# adapter.net
KiCad netlist of a schematic drawn in EAGLE
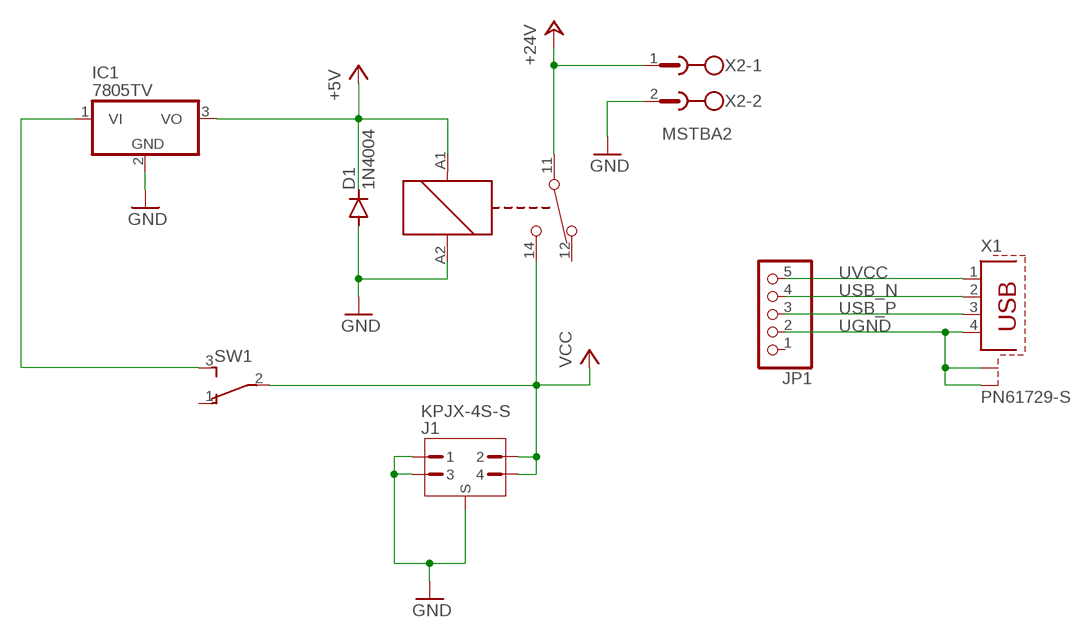
[diagram p0: schematic, sheet 1]

(export (version "E")
  (design (tool "Eeschema 10.0.6"))
  (components
    (comp (ref "D1")
      (value "1N4004")
      (footprint "eagle-import:DO41-10")
      (libsource (lib "eagle-import") (part "1N4004"))
    )
    (comp (ref "IC1")
      (value "7805TV")
      (footprint "eagle-import:TO220V")
      (libsource (lib "eagle-import") (part "78TV05"))
    )
    (comp (ref "J1")
      (value "KPJX-4S-S")
      (footprint "eagle-import:KPJX-4S-S")
      (libsource (lib "eagle-import") (part "KPJX-4S-S"))
    )
    (comp (ref "JP1")
      (value "PINHD-1X5/90")
      (footprint "eagle-import:1X05_90")
      (libsource (lib "eagle-import") (part "PINHD-1X5/90"))
    )
    (comp (ref "K1")
      (value "36.11.9.005.4011")
      (footprint "eagle-import:36.11-4011")
      (libsource (lib "eagle-import") (part "36.11.9.005.4011"))
    )
    (comp (ref "SW1")
      (value "SPDT-90")
      (footprint "eagle-import:SPDT-90")
      (libsource (lib "eagle-import") (part "SPDT-90"))
    )
    (comp (ref "X1")
      (value "PN61729-S")
      (footprint "eagle-import:PN61729-S")
      (libsource (lib "eagle-import") (part "PN61729-S"))
    )
    (comp (ref "X2")
      (value "MSTBA2")
      (footprint "eagle-import:MSTBA2")
      (fields (field (name "MF") "FARNELL") (field (name "MPN") "1757242"))
      (libsource (lib "eagle-import") (part "MSTBA2"))
    )
  )
  (nets
    (net (code "1") (name "+5V") (class "Default")
      (node (ref "D1") (pin "C") (pinfunction "C_C") (pintype "passive"))
      (node (ref "IC1") (pin "3") (pinfunction "VO_3") (pintype "passive"))
      (node (ref "K1") (pin "A1") (pinfunction "1_A1") (pintype "bidirectional"))
    )
    (net (code "2") (name "+24V") (class "Default")
      (node (ref "K1") (pin "11") (pinfunction "3_11") (pintype "bidirectional"))
      (node (ref "X2") (pin "1") (pinfunction "1_1") (pintype "passive"))
    )
    (net (code "3") (name "/UGND") (class "Default")
      (node (ref "JP1") (pin "2") (pinfunction "2_2") (pintype "passive"))
      (node (ref "X1") (pin "4") (pinfunction "4_4") (pintype "passive"))
      (node (ref "X1") (pin "S1") (pinfunction "S1_S1") (pintype "passive"))
      (node (ref "X1") (pin "S2") (pinfunction "S2_S2") (pintype "passive"))
    )
    (net (code "4") (name "/USB_N") (class "Default")
      (node (ref "JP1") (pin "4") (pinfunction "4_4") (pintype "passive"))
      (node (ref "X1") (pin "2") (pinfunction "2_2") (pintype "passive"))
    )
    (net (code "5") (name "/USB_P") (class "Default")
      (node (ref "JP1") (pin "3") (pinfunction "3_3") (pintype "passive"))
      (node (ref "X1") (pin "3") (pinfunction "3_3") (pintype "passive"))
    )
    (net (code "6") (name "/UVCC") (class "Default")
      (node (ref "JP1") (pin "5") (pinfunction "5_5") (pintype "passive"))
      (node (ref "X1") (pin "1") (pinfunction "1_1") (pintype "passive"))
    )
    (net (code "7") (name "GND") (class "Default")
      (node (ref "D1") (pin "A") (pinfunction "A_A") (pintype "passive"))
      (node (ref "IC1") (pin "2") (pinfunction "GND_2") (pintype "passive"))
      (node (ref "J1") (pin "1") (pinfunction "1_1") (pintype "passive"))
      (node (ref "J1") (pin "1A") (pinfunction "1_1A") (pintype "passive"))
      (node (ref "J1") (pin "1B") (pinfunction "1_1B") (pintype "passive"))
      (node (ref "J1") (pin "1C") (pinfunction "1_1C") (pintype "passive"))
      (node (ref "J1") (pin "1D") (pinfunction "1_1D") (pintype "passive"))
      (node (ref "J1") (pin "1E") (pinfunction "1_1E") (pintype "passive"))
      (node (ref "J1") (pin "1F") (pinfunction "1_1F") (pintype "passive"))
      (node (ref "J1") (pin "1G") (pinfunction "1_1G") (pintype "passive"))
      (node (ref "J1") (pin "1H") (pinfunction "1_1H") (pintype "passive"))
      (node (ref "J1") (pin "3") (pinfunction "3_3") (pintype "passive"))
      (node (ref "J1") (pin "3A") (pinfunction "3_3A") (pintype "passive"))
      (node (ref "J1") (pin "3B") (pinfunction "3_3B") (pintype "passive"))
      (node (ref "J1") (pin "3C") (pinfunction "3_3C") (pintype "passive"))
      (node (ref "J1") (pin "3D") (pinfunction "3_3D") (pintype "passive"))
      (node (ref "J1") (pin "3E") (pinfunction "3_3E") (pintype "passive"))
      (node (ref "J1") (pin "3F") (pinfunction "3_3F") (pintype "passive"))
      (node (ref "J1") (pin "3G") (pinfunction "3_3G") (pintype "passive"))
      (node (ref "J1") (pin "3H") (pinfunction "3_3H") (pintype "passive"))
      (node (ref "J1") (pin "S1") (pinfunction "S_S1") (pintype "passive"))
      (node (ref "J1") (pin "S1A") (pinfunction "S_S1A") (pintype "passive"))
      (node (ref "J1") (pin "S1B") (pinfunction "S_S1B") (pintype "passive"))
      (node (ref "J1") (pin "S1C") (pinfunction "S_S1C") (pintype "passive"))
      (node (ref "J1") (pin "S1D") (pinfunction "S_S1D") (pintype "passive"))
      (node (ref "J1") (pin "S1E") (pinfunction "S_S1E") (pintype "passive"))
      (node (ref "J1") (pin "S1F") (pinfunction "S_S1F") (pintype "passive"))
      (node (ref "J1") (pin "S1G") (pinfunction "S_S1G") (pintype "passive"))
      (node (ref "J1") (pin "S1H") (pinfunction "S_S1H") (pintype "passive"))
      (node (ref "J1") (pin "S2") (pinfunction "S_S2") (pintype "passive"))
      (node (ref "J1") (pin "S2A") (pinfunction "S_S2A") (pintype "passive"))
      (node (ref "J1") (pin "S2B") (pinfunction "S_S2B") (pintype "passive"))
      (node (ref "J1") (pin "S2C") (pinfunction "S_S2C") (pintype "passive"))
      (node (ref "J1") (pin "S2D") (pinfunction "S_S2D") (pintype "passive"))
      (node (ref "J1") (pin "S2E") (pinfunction "S_S2E") (pintype "passive"))
      (node (ref "J1") (pin "S2F") (pinfunction "S_S2F") (pintype "passive"))
      (node (ref "J1") (pin "S2G") (pinfunction "S_S2G") (pintype "passive"))
      (node (ref "J1") (pin "S2H") (pinfunction "S_S2H") (pintype "passive"))
      (node (ref "J1") (pin "S3") (pinfunction "S_S3") (pintype "passive"))
      (node (ref "J1") (pin "S4") (pinfunction "S_S4") (pintype "passive"))
      (node (ref "J1") (pin "S5") (pinfunction "S_S5") (pintype "passive"))
      (node (ref "J1") (pin "S5A") (pinfunction "S_S5A") (pintype "passive"))
      (node (ref "J1") (pin "S5B") (pinfunction "S_S5B") (pintype "passive"))
      (node (ref "K1") (pin "A2") (pinfunction "2_A2") (pintype "bidirectional"))
      (node (ref "X2") (pin "2") (pinfunction "1_2") (pintype "passive"))
    )
    (net (code "8") (name "Net-(IC1-VI)") (class "Default")
      (node (ref "IC1") (pin "1") (pinfunction "VI_1") (pintype "input"))
      (node (ref "SW1") (pin "3") (pinfunction "S_3") (pintype "passive"))
    )
    (net (code "9") (name "VCC") (class "Default")
      (node (ref "J1") (pin "2") (pinfunction "2_2") (pintype "passive"))
      (node (ref "J1") (pin "2A") (pinfunction "2_2A") (pintype "passive"))
      (node (ref "J1") (pin "2B") (pinfunction "2_2B") (pintype "passive"))
      (node (ref "J1") (pin "2C") (pinfunction "2_2C") (pintype "passive"))
      (node (ref "J1") (pin "2D") (pinfunction "2_2D") (pintype "passive"))
      (node (ref "J1") (pin "2E") (pinfunction "2_2E") (pintype "passive"))
      (node (ref "J1") (pin "2F") (pinfunction "2_2F") (pintype "passive"))
      (node (ref "J1") (pin "2G") (pinfunction "2_2G") (pintype "passive"))
      (node (ref "J1") (pin "2H") (pinfunction "2_2H") (pintype "passive"))
      (node (ref "J1") (pin "4") (pinfunction "4_4") (pintype "passive"))
      (node (ref "J1") (pin "4A") (pinfunction "4_4A") (pintype "passive"))
      (node (ref "J1") (pin "4B") (pinfunction "4_4B") (pintype "passive"))
      (node (ref "J1") (pin "4C") (pinfunction "4_4C") (pintype "passive"))
      (node (ref "J1") (pin "4D") (pinfunction "4_4D") (pintype "passive"))
      (node (ref "J1") (pin "4E") (pinfunction "4_4E") (pintype "passive"))
      (node (ref "J1") (pin "4F") (pinfunction "4_4F") (pintype "passive"))
      (node (ref "J1") (pin "4G") (pinfunction "4_4G") (pintype "passive"))
      (node (ref "J1") (pin "4H") (pinfunction "4_4H") (pintype "passive"))
      (node (ref "K1") (pin "14") (pinfunction "4_14") (pintype "bidirectional"))
      (node (ref "SW1") (pin "2") (pinfunction "P_2") (pintype "passive"))
    )
    (net (code "10") (name "unconnected-(JP1-Pad1)") (class "Default")
      (node (ref "JP1") (pin "1") (pinfunction "1_1") (pintype "passive"))
    )
    (net (code "11") (name "unconnected-(K1-5-Pad12)") (class "Default")
      (node (ref "K1") (pin "12") (pinfunction "5_12") (pintype "bidirectional"))
    )
    (net (code "12") (name "unconnected-(SW1-O-Pad1)") (class "Default")
      (node (ref "SW1") (pin "1") (pinfunction "O_1") (pintype "passive"))
    )
  )
)
